# mcu_power.net
KiCad netlist of a schematic drawn in Altium Designer
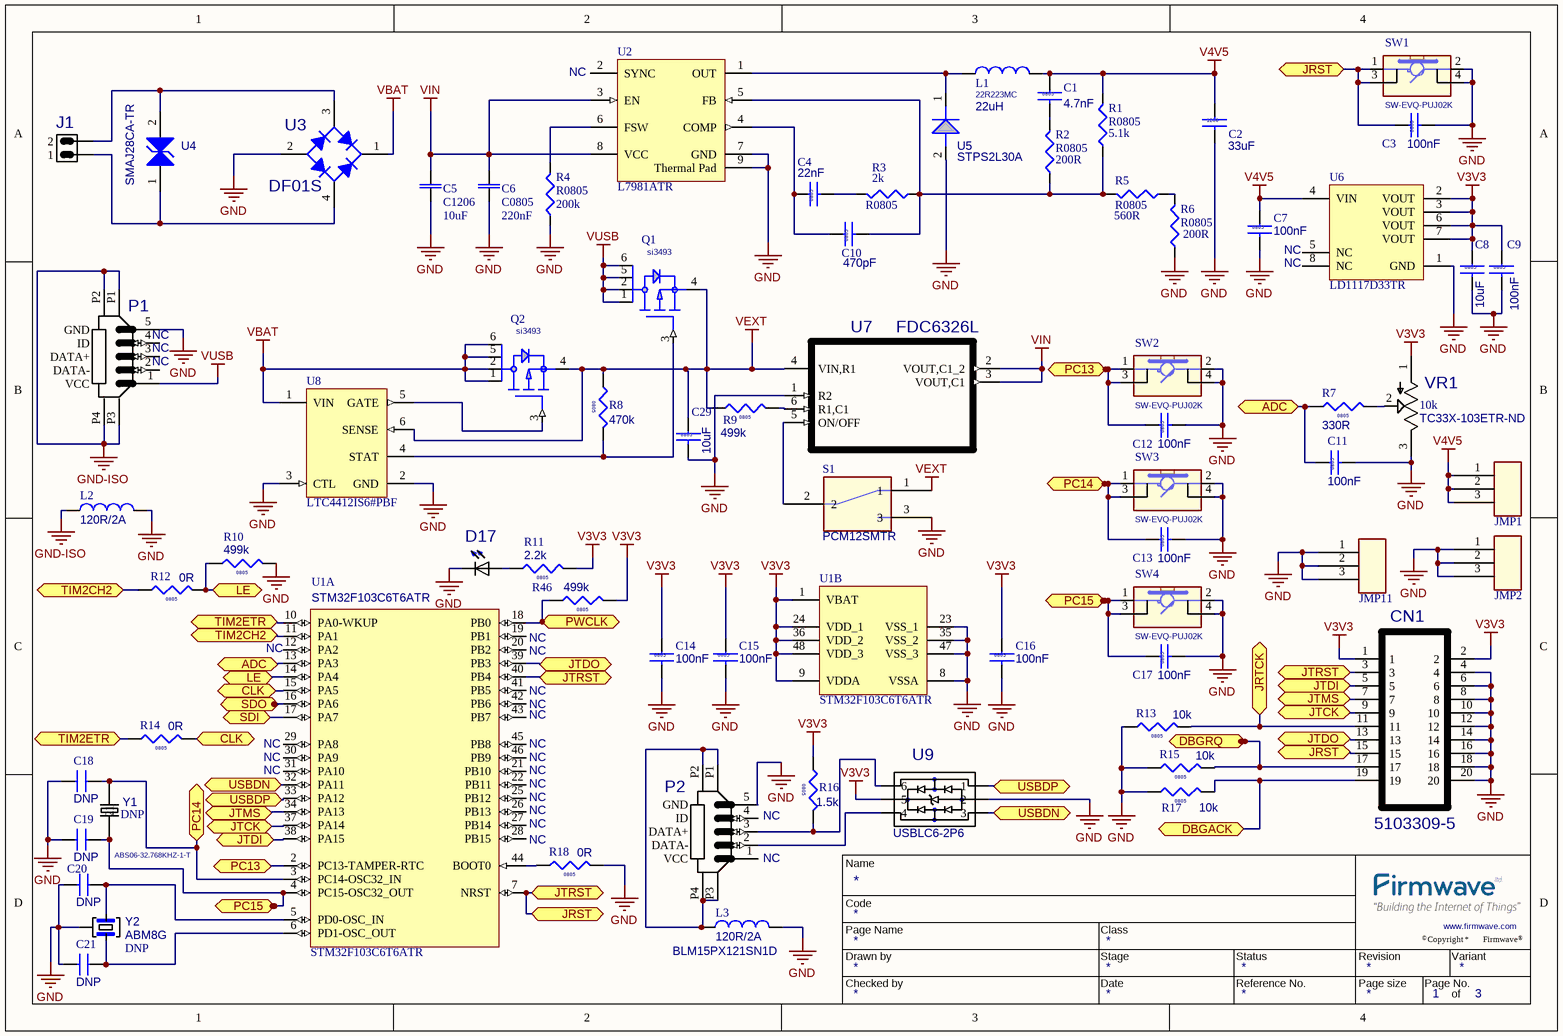
[diagram p0: mcu_power.SchDoc]

(export (version "E")
  (design (tool "Eeschema 10.0.6"))
  (components
    (comp (ref "C1")
      (value "4.7nF")
      (footprint "C0805")
      (fields
        (field (name "TOLERANCE") "±20%")
        (field (name "MANUFACTURER PART NUMBER") "JMK212BJ476MG-T")
        (field (name "MANUFACTURER") "Taiyo Yuden")
      )
      (libsource (lib "Diamond") (part "CAP0805"))
    )
    (comp (ref "C2")
      (value "33uF")
      (footprint "C1206")
      (fields
        (field (name "SELC PARTNUMBER") "SE")
        (field (name "MANUFACTURER") "TDK Corporation")
        (field (name "TOLERANCE") "±20%")
      )
      (libsource (lib "Diamond") (part "CAP1206"))
    )
    (comp (ref "C3")
      (value "100nF")
      (footprint "C0805")
      (fields
        (field (name "TOLERANCE") "±10%")
        (field (name "MANUFACTURER") "Murata Electronics North America")
        (field (name "MANUFACTURER PART NUMBER") "GRM219R71C104KA01D")
      )
      (libsource (lib "Diamond") (part "CAP0805"))
    )
    (comp (ref "C4")
      (value "22nF")
      (footprint "C0805")
      (fields
        (field (name "MANUFACTURER PART NUMBER") "QMK212B7223KG-T")
        (field (name "MANUFACTURER") "Taiyo Yuden")
        (field (name "Comment") "?")
      )
      (libsource (lib "Diamond") (part "CAP0805"))
    )
    (comp (ref "C5")
      (value "C1206")
      (footprint "C1206")
      (description "Capacitor 1206")
      (fields
        (field (name "ALTIUM_VALUE") "10uF")
        (field (name "MANUFACTURER") "TDK Corporation")
        (field (name "TOLERANCE") "±10%")
        (field (name "PUBLISHER") "Firmwave Ltd.")
      )
      (libsource (lib "Diamond") (part "C1206"))
    )
    (comp (ref "C6")
      (value "C0805")
      (footprint "C0805")
      (description "Capacitor 0805")
      (fields
        (field (name "ALTIUM_VALUE") "220nF")
        (field (name "MANUFACTURER") "Taiyo Yuden")
        (field (name "MANUFACTURER PART NUMBER") "UMK212B7224KG-T")
        (field (name "PUBLISHER") "Firmwave Ltd.")
      )
      (libsource (lib "Diamond") (part "C0805"))
    )
    (comp (ref "C7")
      (value "100nF")
      (footprint "C0805")
      (fields
        (field (name "TOLERANCE") "±10%")
        (field (name "MANUFACTURER") "Murata Electronics North America")
        (field (name "MANUFACTURER PART NUMBER") "GRM219R71C104KA01D")
      )
      (libsource (lib "Diamond") (part "CAP0805"))
    )
    (comp (ref "C8")
      (value "10uF")
      (footprint "C0805")
      (fields
        (field (name "TOLERANCE") "±10%")
        (field (name "MANUFACTURER PART NUMBER") "GRM21BR61C106KE15L")
        (field (name "MANUFACTURER") "Murata Electronics North America")
      )
      (libsource (lib "Diamond") (part "CAP0805"))
    )
    (comp (ref "C9")
      (value "100nF")
      (footprint "C0805")
      (fields
        (field (name "TOLERANCE") "±10%")
        (field (name "MANUFACTURER") "Murata Electronics North America")
        (field (name "MANUFACTURER PART NUMBER") "GRM219R71C104KA01D")
      )
      (libsource (lib "Diamond") (part "CAP0805"))
    )
    (comp (ref "C10")
      (value "470pF")
      (footprint "C0805")
      (fields
        (field (name "MANUFACTURER PART NUMBER") "MM051A471JCT2A")
        (field (name "MANUFACTURER") "AVX")
        (field (name "Comment") "?")
      )
      (libsource (lib "Diamond") (part "CAP0805"))
    )
    (comp (ref "C11")
      (value "100nF")
      (footprint "C0805")
      (fields
        (field (name "TOLERANCE") "±10%")
        (field (name "MANUFACTURER") "Murata Electronics North America")
        (field (name "MANUFACTURER PART NUMBER") "GRM219R71C104KA01D")
      )
      (libsource (lib "Diamond") (part "CAP0805"))
    )
    (comp (ref "C12")
      (value "100nF")
      (footprint "C0805")
      (fields
        (field (name "TOLERANCE") "±10%")
        (field (name "MANUFACTURER") "Murata Electronics North America")
        (field (name "MANUFACTURER PART NUMBER") "GRM219R71C104KA01D")
      )
      (libsource (lib "Diamond") (part "CAP0805"))
    )
    (comp (ref "C13")
      (value "100nF")
      (footprint "C0805")
      (fields
        (field (name "TOLERANCE") "±10%")
        (field (name "MANUFACTURER") "Murata Electronics North America")
        (field (name "MANUFACTURER PART NUMBER") "GRM219R71C104KA01D")
      )
      (libsource (lib "Diamond") (part "CAP0805"))
    )
    (comp (ref "C14")
      (value "100nF")
      (footprint "C0805")
      (fields
        (field (name "TOLERANCE") "±10%")
        (field (name "MANUFACTURER") "Murata Electronics North America")
        (field (name "MANUFACTURER PART NUMBER") "GRM219R71C104KA01D")
      )
      (libsource (lib "Diamond") (part "CAP0805"))
    )
    (comp (ref "C15")
      (value "100nF")
      (footprint "C0805")
      (fields
        (field (name "TOLERANCE") "±10%")
        (field (name "MANUFACTURER") "Murata Electronics North America")
        (field (name "MANUFACTURER PART NUMBER") "GRM219R71C104KA01D")
      )
      (libsource (lib "Diamond") (part "CAP0805"))
    )
    (comp (ref "C16")
      (value "100nF")
      (footprint "C0805")
      (fields
        (field (name "TOLERANCE") "±10%")
        (field (name "MANUFACTURER") "Murata Electronics North America")
        (field (name "MANUFACTURER PART NUMBER") "GRM219R71C104KA01D")
      )
      (libsource (lib "Diamond") (part "CAP0805"))
    )
    (comp (ref "C17")
      (value "100nF")
      (footprint "C0805")
      (fields
        (field (name "TOLERANCE") "±10%")
        (field (name "MANUFACTURER") "Murata Electronics North America")
        (field (name "MANUFACTURER PART NUMBER") "GRM219R71C104KA01D")
      )
      (libsource (lib "Diamond") (part "CAP0805"))
    )
    (comp (ref "C18")
      (value "DNP")
      (footprint "0402")
      (description "Ceramic capacitor/SMT0603/16V/20%")
      (fields (field (name "PART") "200xxx") (field (name "Comment") "0402"))
      (libsource (lib "Diamond") (part "C0402_0"))
    )
    (comp (ref "C19")
      (value "DNP")
      (footprint "0402")
      (description "Ceramic capacitor/SMT0603/16V/20%")
      (fields (field (name "PART") "200xxx") (field (name "Comment") "0402"))
      (libsource (lib "Diamond") (part "C0402_0"))
    )
    (comp (ref "C20")
      (value "DNP")
      (footprint "0402")
      (description "Ceramic capacitor/SMT0603/16V/20%")
      (fields (field (name "PART") "200xxx") (field (name "Comment") "0402"))
      (libsource (lib "Diamond") (part "C0402_0"))
    )
    (comp (ref "C21")
      (value "DNP")
      (footprint "0402")
      (description "Ceramic capacitor/SMT0603/16V/20%")
      (fields (field (name "PART") "200xxx") (field (name "Comment") "0402"))
      (libsource (lib "Diamond") (part "C0402_0"))
    )
    (comp (ref "C29")
      (value "10uF")
      (footprint "C0805")
      (fields
        (field (name "TOLERANCE") "±10%")
        (field (name "MANUFACTURER PART NUMBER") "GRM21BR61C106KE15L")
        (field (name "MANUFACTURER") "Murata Electronics North America")
      )
      (libsource (lib "Diamond") (part "CAP0805"))
    )
    (comp (ref "CN1")
      (value "5103309-5")
      (footprint "TYCO_5103309-5")
      (description "Header; Pin; Vertical; Copper Alloy; Thermoplastic; 20; 0.100 x 0.100 in.; 1 A")
      (fields (field (name "MP") "5103309-5") (field (name "MF") "TE Connectivity / AMP"))
      (libsource (lib "Diamond_electromechanical") (part "5103309-5"))
    )
    (comp (ref "D17")
      (value "LTST-C170KGKT")
      (footprint "DIOC200X125X110_LTST-C170KGKT(Primary)")
      (description "Green 2 x 1.25 x 1.1 mm 130Â° Water Clear 35 mcd 2 V Surface Mount LED")
      (fields (field (name "MF") "Lite-On") (field (name "MANUFACTURER PART NUMBER") "LTST-C170KRKT"))
      (libsource (lib "Diamond") (part "LTST-C170KGKT"))
    )
    (comp (ref "J1")
      (value "640455-2")
      (footprint "2-PIN_CONNECTOR")
      (description "MTA-100 2 Position 2.54 mm Single Row Right Angle Wire to Board Header")
      (fields (field (name "MF") "TE Connectivity / AMP"))
      (libsource (lib "Diamond_electromechanical") (part "640455-2"))
    )
    (comp (ref "JMP1")
      (value "JUMPER")
      (footprint "CON-HDR_3X1X254")
      (libsource (lib "Diamond") (part "CON-HDR_3X1X254"))
    )
    (comp (ref "JMP2")
      (value "JUMPER")
      (footprint "CON-HDR_3X1X254")
      (libsource (lib "Diamond") (part "CON-HDR_3X1X254"))
    )
    (comp (ref "JMP11")
      (value "JUMPER")
      (footprint "CON-HDR_3X1X254")
      (libsource (lib "Diamond") (part "CON-HDR_3X1X254"))
    )
    (comp (ref "L1")
      (value "22R223MC")
      (footprint "22R223MC")
      (fields (field (name "MANUFACTURER") "Murata Power Solutions") (field (name "ALTIUM_VALUE") "22uH"))
      (libsource (lib "Diamond") (part "22R223MC"))
    )
    (comp (ref "L2")
      (value "120R/2A")
      (footprint "0402")
      (description "BLM15PX121SN1D")
      (fields
        (field (name "SELC PARTNUMBER") "SE?")
        (field (name "MANUFACTURER") "Murata Electronics North America")
      )
      (libsource (lib "Diamond") (part "IND0402"))
    )
    (comp (ref "L3")
      (value "120R/2A")
      (footprint "0402")
      (description "BLM15PX121SN1D")
      (fields
        (field (name "SELC PARTNUMBER") "SE?")
        (field (name "MANUFACTURER") "Murata Electronics North America")
        (field (name "MANUFACTURER PART NUMBER") "BLM15PX121SN1D")
      )
      (libsource (lib "Diamond") (part "IND0402"))
    )
    (comp (ref "P1")
      (value "440247-2")
      (footprint "TE_440247-2")
      (fields (field (name "MF") "Micross") (field (name "MANUFACTURER") "TE Connectivity AMP Connectors"))
      (libsource (lib "Diamond_electromechanical") (part "440247-2"))
    )
    (comp (ref "P2")
      (value "440247-2")
      (footprint "TE_440247-2")
      (fields (field (name "MF") "Micross") (field (name "MANUFACTURER") "TE Connectivity AMP Connectors"))
      (libsource (lib "Diamond_electromechanical") (part "440247-2"))
    )
    (comp (ref "Q1")
      (value "si3493")
      (footprint "TSOP-6")
      (fields
        (field (name "MANUFACTURER PART NUMBER") "SI3493BDV-T1-E3")
        (field (name "MANUFACTURER") "Vishay Siliconix")
      )
      (libsource (lib "Diamond") (part "SI3493DBV"))
    )
    (comp (ref "Q2")
      (value "si3493")
      (footprint "TSOP-6")
      (fields
        (field (name "MANUFACTURER PART NUMBER") "SI3493BDV-T1-E3")
        (field (name "MANUFACTURER") "Vishay Siliconix")
      )
      (libsource (lib "Diamond") (part "SI3493DBV"))
    )
    (comp (ref "R1")
      (value "R0805")
      (footprint "R0805")
      (fields
        (field (name "ALTIUM_VALUE") "5.1k")
        (field (name "MANUFACTURER") "Panasonic Electronic Components")
        (field (name "MANUFACTURER PART NUMBER") "ERJ-6GEYJ512V")
        (field (name "TOLERANCE") "±5%")
        (field (name "PUBLISHER") "Firmwave Limited")
      )
      (libsource (lib "Diamond") (part "R0805"))
    )
    (comp (ref "R2")
      (value "R0805")
      (footprint "R0805")
      (fields
        (field (name "ALTIUM_VALUE") "200R")
        (field (name "MANUFACTURER") "Panasonic Electronic Components")
        (field (name "TOLERANCE") "±5%")
        (field (name "MANUFACTURER PART NUMBER") "ERJ-6GEYJ201V")
        (field (name "PUBLISHER") "Firmwave Limited")
      )
      (libsource (lib "Diamond") (part "R0805"))
    )
    (comp (ref "R3")
      (value "R0805")
      (footprint "R0805")
      (fields
        (field (name "ALTIUM_VALUE") "2k")
        (field (name "TOLERANCE") "±5%")
        (field (name "MANUFACTURER PART NUMBER") "ERJ-6GEYJ202V")
        (field (name "MANUFACTURER") "Panasonic Electronic Components")
        (field (name "PUBLISHER") "Firmwave Limited")
      )
      (libsource (lib "Diamond") (part "R0805"))
    )
    (comp (ref "R4")
      (value "R0805")
      (footprint "R0805")
      (fields
        (field (name "ALTIUM_VALUE") "200k")
        (field (name "MANUFACTURER") "Panasonic Electronic Components")
        (field (name "MANUFACTURER PART NUMBER") "ERJ-6GEYJ204V")
        (field (name "TOLERANCE") "±5%")
        (field (name "PUBLISHER") "Firmwave Limited")
      )
      (libsource (lib "Diamond") (part "R0805"))
    )
    (comp (ref "R5")
      (value "R0805")
      (footprint "R0805")
      (fields
        (field (name "ALTIUM_VALUE") "560R")
        (field (name "MANUFACTURER") "Panasonic Electronic Components")
        (field (name "TOLERANCE") "±5%")
        (field (name "MANUFACTURER PART NUMBER") "ERJ-6GEYJ561V")
        (field (name "PUBLISHER") "Firmwave Limited")
      )
      (libsource (lib "Diamond") (part "R0805"))
    )
    (comp (ref "R6")
      (value "R0805")
      (footprint "R0805")
      (fields
        (field (name "ALTIUM_VALUE") "200R")
        (field (name "MANUFACTURER") "Panasonic")
        (field (name "MANUFACTURER PART NUMBER") "ERJ-6ENF2200V")
        (field (name "PUBLISHER") "Firmwave Limited")
      )
      (libsource (lib "Diamond") (part "R0805"))
    )
    (comp (ref "R7")
      (value "330R")
      (footprint "R0805")
      (fields
        (field (name "TOLERANCE") "±5%")
        (field (name "MANUFACTURER PART NUMBER") "ERJ-6GEYJ331V")
        (field (name "MANUFACTURER") "Panasonic Electronic Components")
      )
      (libsource (lib "Diamond") (part "RES0805"))
    )
    (comp (ref "R8")
      (value "470k")
      (footprint "R0805")
      (fields
        (field (name "TOLERANCE") "±5%")
        (field (name "MANUFACTURER PART NUMBER") "RCV0805470KJNEA")
        (field (name "MANUFACTURER") "Vishay BC Components")
      )
      (libsource (lib "Diamond") (part "RES0805"))
    )
    (comp (ref "R9")
      (value "499k")
      (footprint "R0805")
      (fields
        (field (name "MANUFACTURER") "Rohm Semiconductor")
        (field (name "TOLERANCE") "±1%")
        (field (name "MANUFACTURER PART NUMBER") "KTR10EZPF4993")
      )
      (libsource (lib "Diamond") (part "RES0805"))
    )
    (comp (ref "R10")
      (value "499k")
      (footprint "R0805")
      (fields
        (field (name "MANUFACTURER") "Rohm Semiconductor")
        (field (name "TOLERANCE") "±1%")
        (field (name "MANUFACTURER PART NUMBER") "KTR10EZPF4993")
      )
      (libsource (lib "Diamond") (part "RES0805"))
    )
    (comp (ref "R11")
      (value "2.2k")
      (footprint "R0805")
      (fields
        (field (name "MANUFACTURER") "Vishay")
        (field (name "TOLERANCE") "±1%")
        (field (name "MANUFACTURER PART NUMBER") "CRCW08052K20FKEA")
      )
      (libsource (lib "Diamond") (part "RES0805"))
    )
    (comp (ref "R12")
      (value "0R")
      (footprint "R0805")
      (fields
        (field (name "MANUFACTURER PART NUMBER") "CRCW08050000Z0EA")
        (field (name "MANUFACTURER") "Vishay Dale")
        (field (name "TOLERANCE") "Jumper")
      )
      (libsource (lib "Diamond") (part "RES0805"))
    )
    (comp (ref "R13")
      (value "10k")
      (footprint "R0805")
      (fields
        (field (name "MANUFACTURER PART NUMBER") "CRCW080510K0FKEA")
        (field (name "TOLERANCE") "±1%")
        (field (name "MANUFACTURER") "Vishay Dale")
      )
      (libsource (lib "Diamond") (part "RES0805"))
    )
    (comp (ref "R14")
      (value "0R")
      (footprint "R0805")
      (fields
        (field (name "MANUFACTURER PART NUMBER") "CRCW08050000Z0EA")
        (field (name "MANUFACTURER") "Vishay Dale")
        (field (name "TOLERANCE") "Jumper")
      )
      (libsource (lib "Diamond") (part "RES0805"))
    )
    (comp (ref "R15")
      (value "10k")
      (footprint "R0805")
      (fields
        (field (name "MANUFACTURER PART NUMBER") "CRCW080510K0FKEA")
        (field (name "TOLERANCE") "±1%")
        (field (name "MANUFACTURER") "Vishay Dale")
      )
      (libsource (lib "Diamond") (part "RES0805"))
    )
    (comp (ref "R16")
      (value "1.5k")
      (footprint "R0805")
      (fields
        (field (name "MANUFACTURER") "Vishay Dale")
        (field (name "TOLERANCE") "±1%")
        (field (name "MANUFACTURER PART NUMBER") "CRCW08051K50FKEA")
      )
      (libsource (lib "Diamond") (part "RES0805"))
    )
    (comp (ref "R17")
      (value "10k")
      (footprint "R0805")
      (fields
        (field (name "MANUFACTURER PART NUMBER") "CRCW080510K0FKEA")
        (field (name "TOLERANCE") "±1%")
        (field (name "MANUFACTURER") "Vishay Dale")
      )
      (libsource (lib "Diamond") (part "RES0805"))
    )
    (comp (ref "R18")
      (value "0R")
      (footprint "R0805")
      (fields
        (field (name "MANUFACTURER PART NUMBER") "CRCW08050000Z0EA")
        (field (name "MANUFACTURER") "Vishay Dale")
        (field (name "TOLERANCE") "Jumper")
      )
      (libsource (lib "Diamond") (part "RES0805"))
    )
    (comp (ref "R46")
      (value "499k")
      (footprint "R0805")
      (fields
        (field (name "MANUFACTURER") "Rohm Semiconductor")
        (field (name "TOLERANCE") "±1%")
        (field (name "MANUFACTURER PART NUMBER") "KTR10EZPF4993")
      )
      (libsource (lib "Diamond") (part "RES0805"))
    )
    (comp (ref "S1")
      (value "SW_ON_OFF_Mini")
      (footprint "PCM12SMTR")
      (fields (field (name "MANUFACTURER PART NUMBER") "PCM12SMTR") (field (name "MANUFACTURER") "C&K"))
      (libsource (lib "Diamond") (part "SW_ON_OFF_Mini"))
    )
    (comp (ref "SW1")
      (value "SW-EVQ-PUJ02K")
      (footprint "EVQPUJ02K")
      (description "EVQ-PUJ02K")
      (fields (field (name "MANUFACTURER") "Panasonic Electronic Components"))
      (libsource (lib "Diamond") (part "SW-EVQ-PUJ02K"))
    )
    (comp (ref "SW2")
      (value "SW-EVQ-PUJ02K")
      (footprint "EVQPUJ02K")
      (description "EVQ-PUJ02K")
      (fields (field (name "MANUFACTURER") "Panasonic Electronic Components"))
      (libsource (lib "Diamond") (part "SW-EVQ-PUJ02K"))
    )
    (comp (ref "SW3")
      (value "SW-EVQ-PUJ02K")
      (footprint "EVQPUJ02K")
      (description "EVQ-PUJ02K")
      (fields (field (name "MANUFACTURER") "Panasonic Electronic Components"))
      (libsource (lib "Diamond") (part "SW-EVQ-PUJ02K"))
    )
    (comp (ref "SW4")
      (value "SW-EVQ-PUJ02K")
      (footprint "EVQPUJ02K")
      (description "EVQ-PUJ02K")
      (fields (field (name "MANUFACTURER") "Panasonic Electronic Components"))
      (libsource (lib "Diamond") (part "SW-EVQ-PUJ02K"))
    )
    (comp (ref "U1")
      (value "STM32F103C6T6ATR")
      (footprint "STM-LQFP48_N")
      (fields
        (field (name "MANUFACTURER PART NUMBER") "STM32F103C6T6ATR")
        (field (name "MANUFACTURER") "STMicroelectronics")
      )
      (libsource (lib "STMicroelectronics STM32 F1") (part "STM32F103C6T6ATR"))
    )
    (comp (ref "U2")
      (value "L7981ATR")
      (footprint "HSOP8-D1_N")
      (description "3 A step-down switching regulator, 8-Pin HSOP, Tape and Reel")
      (fields (field (name "MANUFACTURER") "STMicroelectronics"))
      (libsource (lib "STMicroelectronics Power Management DC-DC Conversion") (part "L7981ATR"))
    )
    (comp (ref "U3")
      (value "DF01S")
      (footprint "SOT508P985X260-4N")
      (description "Power Management, Bridge Rectifiers, Semiconductors and Actives")
      (fields
        (field (name "MF") "International Rectifier")
        (field (name "MANUFACTURER") "Vishay Semiconductor")
      )
      (libsource (lib "Diamond") (part "DF01S"))
    )
    (comp (ref "U4")
      (value "SMAJ28CA-TR")
      (footprint "DO-214AA")
      (fields (field (name "MANUFACTURER") "STMICROELECTRONICS"))
      (libsource (lib "Diamond") (part "SMAJ28CA-TR"))
    )
    (comp (ref "U5")
      (value "STPS2L30A")
      (footprint "DO-214AA")
      (fields (field (name "MANUFACTURER") "NXP Semiconductors") (field (name "MPN") "BGU7005"))
      (libsource (lib "Diamond") (part "STPS2L30A"))
    )
    (comp (ref "U6")
      (value "LD1117D33TR")
      (footprint "SO8_N")
      (description "Fixed Low Drop Positive Voltage Regulator, 3.3V, 8-Pin SO, Tape and Reel")
      (fields
        (field (name "MANUFACTURER PART NUMBER") "STPS2L30A")
        (field (name "MANUFACTURER") "STMicroelectronics")
      )
      (libsource (lib "STMicroelectronics Power Management Linear Regulator") (part "LD1117D33TR"))
    )
    (comp (ref "U7")
      (value "FDC6326L")
      (footprint "SOT95P280X110-6N")
      (description "FDC6326L Series 20 V 0.125 Ohm Surface Mount Integrated Load Switch -SuperSOT-6")
      (fields
        (field (name "MF") "Fairchild Semiconductor")
        (field (name "MANUFACTURER PART NUMBER") "FDC6331L")
      )
      (libsource (lib "Diamond_semiconductors") (part "FDC6326L"))
    )
    (comp (ref "U8")
      (value "LTC4412IS6#PBF")
      (footprint "LT-S6-6-TSOT-23_N")
      (description "Low Loss PowerPath(TM) Controller, 2.5 to 28 V Vin, 6-pin SOT23 (S6-6), -40 to 85 degC, Pb-Free")
      (fields (field (name "MANUFACTURER") "Linear Technology"))
      (libsource (lib "Linear Technology Power Management Power Control") (part "LTC4412IS6#PBF"))
    )
    (comp (ref "U9")
      (value "USBLC6-2")
      (footprint "USBLC6-2P6")
      (description "Very Low Capacitance Esd Protection")
      (fields (field (name "MF") "STMicroelectronics") (field (name "MANUFACTURER PART NUMBER") "USBLC6-2P6"))
      (libsource (lib "Diamond") (part "USBLC6-2"))
    )
    (comp (ref "VR1")
      (value "10k")
      (footprint "TRIM_TC33X-2-103E")
      (description "Res Trimmer 10K Ohm 25% 0.1W(1/10W) 1(Elec)/1(Mech)Turn (3 X 3.8mm) Foot Print SMD Embossed T/R")
      (fields
        (field (name "MP") "TC33X-2-103E")
        (field (name "MF") "Bourns")
        (field (name "SUPPLIER PART NUMBER") "TC33X-103ETR-ND")
      )
      (libsource (lib "Diamond_passive") (part "TC33X-2-103E"))
    )
    (comp (ref "Y1")
      (value "ABS06-32.768KHZ-1-T")
      (footprint "XTAL_ABS06-32.768KHZ-1-T")
      (fields (field (name "ALTIUM_VALUE") "DNP"))
      (libsource (lib "Diamond") (part "ABS06-32.768KHZ-1-T"))
    )
    (comp (ref "Y2")
      (value "ABM8G")
      (footprint "ABM8G_ABM8G(Primary)")
      (fields (field (name "ALTIUM_VALUE") "DNP"))
      (libsource (lib "Diamond") (part "ABM8G"))
    )
  )
  (nets
    (net (code "1") (name "/ADC") (class "Default")
      (node (ref "C11") (pin "1") (pinfunction "1_1") (pintype "passive"))
      (node (ref "R7") (pin "1") (pinfunction "1_1") (pintype "passive"))
      (node (ref "U1") (pin "13") (pinfunction "PA3_13") (pintype "bidirectional"))
    )
    (net (code "2") (name "/CLK") (class "Default")
      (node (ref "R14") (pin "2") (pinfunction "2_2") (pintype "passive"))
      (node (ref "U1") (pin "15") (pinfunction "PA5_15") (pintype "bidirectional"))
    )
    (net (code "3") (name "/DBGACK") (class "Default")
      (node (ref "CN1") (pin "19") (pinfunction "19_19") (pintype "passive"))
      (node (ref "R17") (pin "2") (pinfunction "2_2") (pintype "passive"))
    )
    (net (code "4") (name "/DBGRQ") (class "Default")
      (node (ref "CN1") (pin "17") (pinfunction "17_17") (pintype "passive"))
      (node (ref "R15") (pin "2") (pinfunction "2_2") (pintype "passive"))
    )
    (net (code "5") (name "/JRST") (class "Default")
      (node (ref "C3") (pin "1") (pinfunction "1_1") (pintype "passive"))
      (node (ref "CN1") (pin "15") (pinfunction "15_15") (pintype "passive"))
      (node (ref "CN1") (pin "3") (pinfunction "3_3") (pintype "passive"))
      (node (ref "SW1") (pin "1") (pinfunction "1_1") (pintype "passive"))
      (node (ref "SW1") (pin "3") (pinfunction "3_3") (pintype "passive"))
      (node (ref "U1") (pin "40") (pinfunction "PB4_40") (pintype "bidirectional"))
      (node (ref "U1") (pin "7") (pinfunction "NRST_7") (pintype "bidirectional"))
    )
    (net (code "6") (name "/JRTCK") (class "Default")
      (node (ref "CN1") (pin "11") (pinfunction "11_11") (pintype "passive"))
      (node (ref "R13") (pin "2") (pinfunction "2_2") (pintype "passive"))
    )
    (net (code "7") (name "/JTCK") (class "Default")
      (node (ref "CN1") (pin "9") (pinfunction "9_9") (pintype "passive"))
      (node (ref "U1") (pin "37") (pinfunction "PA14_37") (pintype "bidirectional"))
    )
    (net (code "8") (name "/JTDI") (class "Default")
      (node (ref "CN1") (pin "5") (pinfunction "5_5") (pintype "passive"))
      (node (ref "U1") (pin "38") (pinfunction "PA15_38") (pintype "bidirectional"))
    )
    (net (code "9") (name "/JTDO") (class "Default")
      (node (ref "CN1") (pin "13") (pinfunction "13_13") (pintype "passive"))
      (node (ref "U1") (pin "39") (pinfunction "PB3_39") (pintype "bidirectional"))
    )
    (net (code "10") (name "/JTMS") (class "Default")
      (node (ref "CN1") (pin "7") (pinfunction "7_7") (pintype "passive"))
      (node (ref "U1") (pin "34") (pinfunction "PA13_34") (pintype "bidirectional"))
    )
    (net (code "11") (name "/LE") (class "Default")
      (node (ref "R10") (pin "1") (pinfunction "1_1") (pintype "passive"))
      (node (ref "R12") (pin "2") (pinfunction "2_2") (pintype "passive"))
      (node (ref "U1") (pin "14") (pinfunction "PA4_14") (pintype "bidirectional"))
    )
    (net (code "12") (name "/PC13") (class "Default")
      (node (ref "C12") (pin "1") (pinfunction "1_1") (pintype "passive"))
      (node (ref "SW2") (pin "1") (pinfunction "1_1") (pintype "passive"))
      (node (ref "SW2") (pin "3") (pinfunction "3_3") (pintype "passive"))
      (node (ref "U1") (pin "2") (pinfunction "PC13-TAMPER-RTC_2") (pintype "bidirectional"))
    )
    (net (code "13") (name "/PC14") (class "Default")
      (node (ref "C13") (pin "1") (pinfunction "1_1") (pintype "passive"))
      (node (ref "C18") (pin "2") (pinfunction "2_2") (pintype "passive"))
      (node (ref "SW3") (pin "1") (pinfunction "1_1") (pintype "passive"))
      (node (ref "SW3") (pin "3") (pinfunction "3_3") (pintype "passive"))
      (node (ref "U1") (pin "3") (pinfunction "PC14-OSC32_IN_3") (pintype "bidirectional"))
      (node (ref "Y1") (pin "1") (pinfunction "1_1") (pintype "passive"))
    )
    (net (code "14") (name "/PC15") (class "Default")
      (node (ref "C17") (pin "1") (pinfunction "1_1") (pintype "passive"))
      (node (ref "C19") (pin "2") (pinfunction "2_2") (pintype "passive"))
      (node (ref "SW4") (pin "1") (pinfunction "1_1") (pintype "passive"))
      (node (ref "SW4") (pin "3") (pinfunction "3_3") (pintype "passive"))
      (node (ref "U1") (pin "4") (pinfunction "PC15-OSC32_OUT_4") (pintype "bidirectional"))
      (node (ref "Y1") (pin "2") (pinfunction "2_2") (pintype "passive"))
    )
    (net (code "15") (name "/PWCLK") (class "Default")
      (node (ref "R46") (pin "1") (pinfunction "1_1") (pintype "passive"))
      (node (ref "U1") (pin "18") (pinfunction "PB0_18") (pintype "bidirectional"))
    )
    (net (code "16") (name "/SDI") (class "Default")
      (node (ref "U1") (pin "17") (pinfunction "PA7_17") (pintype "bidirectional"))
    )
    (net (code "17") (name "/SDO") (class "Default")
      (node (ref "U1") (pin "16") (pinfunction "PA6_16") (pintype "bidirectional"))
    )
    (net (code "18") (name "/TIM2CH2") (class "Default")
      (node (ref "R12") (pin "1") (pinfunction "1_1") (pintype "passive"))
      (node (ref "U1") (pin "11") (pinfunction "PA1_11") (pintype "bidirectional"))
    )
    (net (code "19") (name "/TIM2ETR") (class "Default")
      (node (ref "R14") (pin "1") (pinfunction "1_1") (pintype "passive"))
      (node (ref "U1") (pin "10") (pinfunction "PA0-WKUP_10") (pintype "bidirectional"))
    )
    (net (code "20") (name "/USBDN") (class "Default")
      (node (ref "U1") (pin "32") (pinfunction "PA11_32") (pintype "bidirectional"))
      (node (ref "U9") (pin "3") (pinfunction "3_3") (pintype "bidirectional"))
    )
    (net (code "21") (name "/USBDP") (class "Default")
      (node (ref "U1") (pin "33") (pinfunction "PA12_33") (pintype "bidirectional"))
      (node (ref "U9") (pin "1") (pinfunction "1_1") (pintype "bidirectional"))
    )
    (net (code "22") (name "GND") (class "Default")
      (node (ref "C11") (pin "2") (pinfunction "2_2") (pintype "passive"))
      (node (ref "C12") (pin "2") (pinfunction "2_2") (pintype "passive"))
      (node (ref "C13") (pin "2") (pinfunction "2_2") (pintype "passive"))
      (node (ref "C14") (pin "2") (pinfunction "2_2") (pintype "passive"))
      (node (ref "C15") (pin "2") (pinfunction "2_2") (pintype "passive"))
      (node (ref "C16") (pin "2") (pinfunction "2_2") (pintype "passive"))
      (node (ref "C17") (pin "2") (pinfunction "2_2") (pintype "passive"))
      (node (ref "C18") (pin "1") (pinfunction "1_1") (pintype "passive"))
      (node (ref "C19") (pin "1") (pinfunction "1_1") (pintype "passive"))
      (node (ref "C2") (pin "2") (pinfunction "2_2") (pintype "passive"))
      (node (ref "C20") (pin "1") (pinfunction "1_1") (pintype "passive"))
      (node (ref "C21") (pin "1") (pinfunction "1_1") (pintype "passive"))
      (node (ref "C29") (pin "2") (pinfunction "2_2") (pintype "passive"))
      (node (ref "C3") (pin "2") (pinfunction "2_2") (pintype "passive"))
      (node (ref "C5") (pin "1") (pinfunction "1_1") (pintype "passive"))
      (node (ref "C6") (pin "1") (pinfunction "1_1") (pintype "passive"))
      (node (ref "C7") (pin "2") (pinfunction "2_2") (pintype "passive"))
      (node (ref "C8") (pin "2") (pinfunction "2_2") (pintype "passive"))
      (node (ref "C9") (pin "2") (pinfunction "2_2") (pintype "passive"))
      (node (ref "CN1") (pin "10") (pinfunction "10_10") (pintype "passive"))
      (node (ref "CN1") (pin "12") (pinfunction "12_12") (pintype "passive"))
      (node (ref "CN1") (pin "14") (pinfunction "14_14") (pintype "passive"))
      (node (ref "CN1") (pin "16") (pinfunction "16_16") (pintype "passive"))
      (node (ref "CN1") (pin "18") (pinfunction "18_18") (pintype "passive"))
      (node (ref "CN1") (pin "20") (pinfunction "20_20") (pintype "passive"))
      (node (ref "CN1") (pin "4") (pinfunction "4_4") (pintype "passive"))
      (node (ref "CN1") (pin "6") (pinfunction "6_6") (pintype "passive"))
      (node (ref "CN1") (pin "8") (pinfunction "8_8") (pintype "passive"))
      (node (ref "D17") (pin "1") (pinfunction "1_1") (pintype "passive"))
      (node (ref "JMP11") (pin "1") (pinfunction "1_1") (pintype "passive"))
      (node (ref "JMP11") (pin "2") (pinfunction "2_2") (pintype "passive"))
      (node (ref "JMP11") (pin "3") (pinfunction "3_3") (pintype "passive"))
      (node (ref "JMP2") (pin "1") (pinfunction "1_1") (pintype "passive"))
      (node (ref "JMP2") (pin "2") (pinfunction "2_2") (pintype "passive"))
      (node (ref "JMP2") (pin "3") (pinfunction "3_3") (pintype "passive"))
      (node (ref "L2") (pin "2") (pinfunction "2_2") (pintype "passive"))
      (node (ref "L3") (pin "2") (pinfunction "2_2") (pintype "passive"))
      (node (ref "P1") (pin "5") (pinfunction "GND_5") (pintype "passive"))
      (node (ref "P2") (pin "5") (pinfunction "GND_5") (pintype "passive"))
      (node (ref "R10") (pin "2") (pinfunction "2_2") (pintype "passive"))
      (node (ref "R13") (pin "1") (pinfunction "1_1") (pintype "passive"))
      (node (ref "R15") (pin "1") (pinfunction "1_1") (pintype "passive"))
      (node (ref "R17") (pin "1") (pinfunction "1_1") (pintype "passive"))
      (node (ref "R18") (pin "2") (pinfunction "2_2") (pintype "passive"))
      (node (ref "R4") (pin "1") (pinfunction "1_1") (pintype "passive"))
      (node (ref "R6") (pin "1") (pinfunction "1_1") (pintype "passive"))
      (node (ref "S1") (pin "3") (pinfunction "3_3") (pintype "passive"))
      (node (ref "SW1") (pin "2") (pinfunction "2_2") (pintype "passive"))
      (node (ref "SW1") (pin "4") (pinfunction "4_4") (pintype "passive"))
      (node (ref "SW2") (pin "2") (pinfunction "2_2") (pintype "passive"))
      (node (ref "SW2") (pin "4") (pinfunction "4_4") (pintype "passive"))
      (node (ref "SW3") (pin "2") (pinfunction "2_2") (pintype "passive"))
      (node (ref "SW3") (pin "4") (pinfunction "4_4") (pintype "passive"))
      (node (ref "SW4") (pin "2") (pinfunction "2_2") (pintype "passive"))
      (node (ref "SW4") (pin "4") (pinfunction "4_4") (pintype "passive"))
      (node (ref "U1") (pin "23") (pinfunction "VSS_1_23") (pintype "power_in"))
      (node (ref "U1") (pin "35") (pinfunction "VSS_2_35") (pintype "power_in"))
      (node (ref "U1") (pin "47") (pinfunction "VSS_3_47") (pintype "power_in"))
      (node (ref "U1") (pin "8") (pinfunction "VSSA_8") (pintype "power_in"))
      (node (ref "U2") (pin "7") (pinfunction "GND_7") (pintype "power_in"))
      (node (ref "U2") (pin "9") (pinfunction "Thermal_Pad_9") (pintype "power_in"))
      (node (ref "U3") (pin "2") (pinfunction "A_2") (pintype "passive"))
      (node (ref "U5") (pin "2") (pinfunction "ANODE_2") (pintype "passive"))
      (node (ref "U6") (pin "1") (pinfunction "GND_1") (pintype "power_in"))
      (node (ref "U7") (pin "1") (pinfunction "R2_1") (pintype "input"))
      (node (ref "U8") (pin "2") (pinfunction "GND_2") (pintype "power_in"))
      (node (ref "U8") (pin "3") (pinfunction "CTL_3") (pintype "input"))
      (node (ref "U9") (pin "2") (pinfunction "2_2") (pintype "power_in"))
      (node (ref "VR1") (pin "3") (pinfunction "3_3") (pintype "passive"))
      (node (ref "Y2") (pin "2_4") (pinfunction "2_2_4") (pintype "passive"))
    )
    (net (code "23") (name "GND-ISO") (class "Default")
      (node (ref "L2") (pin "1") (pinfunction "1_1") (pintype "passive"))
      (node (ref "P1") (pin "P1") (pinfunction "GND_P1") (pintype "passive"))
      (node (ref "P1") (pin "P2") (pinfunction "GND_P2") (pintype "passive"))
      (node (ref "P1") (pin "P3") (pinfunction "GND_P3") (pintype "passive"))
      (node (ref "P1") (pin "P4") (pinfunction "GND_P4") (pintype "passive"))
    )
    (net (code "24") (name "Net-(C1-Pad2)") (class "Default")
      (node (ref "C1") (pin "2") (pinfunction "2_2") (pintype "passive"))
      (node (ref "R2") (pin "2") (pinfunction "2_2") (pintype "passive"))
    )
    (net (code "25") (name "Net-(C4-Pad2)") (class "Default")
      (node (ref "C4") (pin "2") (pinfunction "2_2") (pintype "passive"))
      (node (ref "R3") (pin "2") (pinfunction "2_2") (pintype "passive"))
    )
    (net (code "26") (name "Net-(D17-Pad2)") (class "Default")
      (node (ref "D17") (pin "2") (pinfunction "2_2") (pintype "passive"))
      (node (ref "R11") (pin "1") (pinfunction "1_1") (pintype "passive"))
    )
    (net (code "27") (name "Net-(J1-Pad1)") (class "Default")
      (node (ref "J1") (pin "1") (pinfunction "1_1") (pintype "passive"))
      (node (ref "U3") (pin "4") (pinfunction "C_4") (pintype "passive"))
      (node (ref "U4") (pin "1") (pinfunction "C_1") (pintype "passive"))
    )
    (net (code "28") (name "Net-(J1-Pad2)") (class "Default")
      (node (ref "J1") (pin "2") (pinfunction "2_2") (pintype "passive"))
      (node (ref "U3") (pin "3") (pinfunction "C_3") (pintype "passive"))
      (node (ref "U4") (pin "2") (pinfunction "C_2") (pintype "passive"))
    )
    (net (code "29") (name "Net-(L3-Pad1)") (class "Default")
      (node (ref "L3") (pin "1") (pinfunction "1_1") (pintype "passive"))
      (node (ref "P2") (pin "P1") (pinfunction "GND_P1") (pintype "passive"))
      (node (ref "P2") (pin "P2") (pinfunction "GND_P2") (pintype "passive"))
      (node (ref "P2") (pin "P3") (pinfunction "GND_P3") (pintype "passive"))
      (node (ref "P2") (pin "P4") (pinfunction "GND_P4") (pintype "passive"))
    )
    (net (code "30") (name "Net-(P2-DATA+)") (class "Default")
      (node (ref "P2") (pin "3") (pinfunction "DATA+_3") (pintype "bidirectional"))
      (node (ref "R16") (pin "2") (pinfunction "2_2") (pintype "passive"))
      (node (ref "U9") (pin "6") (pinfunction "6_6") (pintype "bidirectional"))
    )
    (net (code "31") (name "Net-(P2-DATA-)") (class "Default")
      (node (ref "P2") (pin "2") (pinfunction "DATA-_2") (pintype "bidirectional"))
      (node (ref "U9") (pin "4") (pinfunction "4_4") (pintype "bidirectional"))
    )
    (net (code "32") (name "Net-(Q1-G)") (class "Default")
      (node (ref "Q1") (pin "3") (pinfunction "G_3") (pintype "input"))
      (node (ref "R8") (pin "2") (pinfunction "2_2") (pintype "passive"))
      (node (ref "U8") (pin "4") (pinfunction "STAT_4") (pintype "open_collector"))
    )
    (net (code "33") (name "Net-(Q2-G)") (class "Default")
      (node (ref "Q2") (pin "3") (pinfunction "G_3") (pintype "input"))
      (node (ref "U8") (pin "5") (pinfunction "GATE_5") (pintype "output"))
    )
    (net (code "34") (name "Net-(R5-Pad1)") (class "Default")
      (node (ref "R5") (pin "1") (pinfunction "1_1") (pintype "passive"))
      (node (ref "R6") (pin "2") (pinfunction "2_2") (pintype "passive"))
    )
    (net (code "35") (name "Net-(R7-Pad2)") (class "Default")
      (node (ref "R7") (pin "2") (pinfunction "2_2") (pintype "passive"))
      (node (ref "VR1") (pin "2") (pinfunction "2_2") (pintype "passive"))
    )
    (net (code "36") (name "Net-(U1A-BOOT0)") (class "Default")
      (node (ref "R18") (pin "1") (pinfunction "1_1") (pintype "passive"))
      (node (ref "U1") (pin "44") (pinfunction "BOOT0_44") (pintype "input"))
    )
    (net (code "37") (name "Net-(U1A-PD0-OSC_IN)") (class "Default")
      (node (ref "C20") (pin "2") (pinfunction "2_2") (pintype "passive"))
      (node (ref "U1") (pin "5") (pinfunction "PD0-OSC_IN_5") (pintype "bidirectional"))
      (node (ref "Y2") (pin "1") (pinfunction "1_1") (pintype "passive"))
    )
    (net (code "38") (name "Net-(U1A-PD1-OSC_OUT)") (class "Default")
      (node (ref "C21") (pin "2") (pinfunction "2_2") (pintype "passive"))
      (node (ref "U1") (pin "6") (pinfunction "PD1-OSC_OUT_6") (pintype "bidirectional"))
      (node (ref "Y2") (pin "3") (pinfunction "3_3") (pintype "passive"))
    )
    (net (code "39") (name "Net-(U2-COMP)") (class "Default")
      (node (ref "C10") (pin "1") (pinfunction "1_1") (pintype "passive"))
      (node (ref "C4") (pin "1") (pinfunction "1_1") (pintype "passive"))
      (node (ref "U2") (pin "4") (pinfunction "COMP_4") (pintype "output"))
    )
    (net (code "40") (name "Net-(U2-FB)") (class "Default")
      (node (ref "C10") (pin "2") (pinfunction "2_2") (pintype "passive"))
      (node (ref "R1") (pin "1") (pinfunction "1_1") (pintype "passive"))
      (node (ref "R2") (pin "1") (pinfunction "1_1") (pintype "passive"))
      (node (ref "R3") (pin "1") (pinfunction "1_1") (pintype "passive"))
      (node (ref "R5") (pin "2") (pinfunction "2_2") (pintype "passive"))
      (node (ref "U2") (pin "5") (pinfunction "FB_5") (pintype "input"))
    )
    (net (code "41") (name "Net-(U2-FSW)") (class "Default")
      (node (ref "R4") (pin "2") (pinfunction "2_2") (pintype "passive"))
      (node (ref "U2") (pin "6") (pinfunction "FSW_6") (pintype "passive"))
    )
    (net (code "42") (name "Net-(U2-OUT)") (class "Default")
      (node (ref "L1") (pin "1") (pinfunction "1_1") (pintype "passive"))
      (node (ref "U2") (pin "1") (pinfunction "OUT_1") (pintype "power_in"))
      (node (ref "U5") (pin "1") (pinfunction "CATHODE_1") (pintype "passive"))
    )
    (net (code "43") (name "Net-(U7-ON{slash}OFF)") (class "Default")
      (node (ref "S1") (pin "2") (pinfunction "2_2") (pintype "passive"))
      (node (ref "U7") (pin "5") (pinfunction "ON/OFF_5") (pintype "input"))
    )
    (net (code "44") (name "Net-(U7-R1,C1)") (class "Default")
      (node (ref "R9") (pin "2") (pinfunction "2_2") (pintype "passive"))
      (node (ref "U7") (pin "6") (pinfunction "R1,C1_6") (pintype "input"))
    )
    (net (code "45") (name "V3V3") (class "Default")
      (node (ref "C14") (pin "1") (pinfunction "1_1") (pintype "passive"))
      (node (ref "C15") (pin "1") (pinfunction "1_1") (pintype "passive"))
      (node (ref "C16") (pin "1") (pinfunction "1_1") (pintype "passive"))
      (node (ref "C8") (pin "1") (pinfunction "1_1") (pintype "passive"))
      (node (ref "C9") (pin "1") (pinfunction "1_1") (pintype "passive"))
      (node (ref "CN1") (pin "1") (pinfunction "1_1") (pintype "passive"))
      (node (ref "CN1") (pin "2") (pinfunction "2_2") (pintype "passive"))
      (node (ref "R11") (pin "2") (pinfunction "2_2") (pintype "passive"))
      (node (ref "R16") (pin "1") (pinfunction "1_1") (pintype "passive"))
      (node (ref "R46") (pin "2") (pinfunction "2_2") (pintype "passive"))
      (node (ref "U1") (pin "1") (pinfunction "VBAT_1") (pintype "power_in"))
      (node (ref "U1") (pin "24") (pinfunction "VDD_1_24") (pintype "power_in"))
      (node (ref "U1") (pin "36") (pinfunction "VDD_2_36") (pintype "power_in"))
      (node (ref "U1") (pin "48") (pinfunction "VDD_3_48") (pintype "power_in"))
      (node (ref "U1") (pin "9") (pinfunction "VDDA_9") (pintype "power_in"))
      (node (ref "U6") (pin "2") (pinfunction "VOUT_2") (pintype "power_in"))
      (node (ref "U6") (pin "3") (pinfunction "VOUT_3") (pintype "power_in"))
      (node (ref "U6") (pin "6") (pinfunction "VOUT_6") (pintype "power_in"))
      (node (ref "U6") (pin "7") (pinfunction "VOUT_7") (pintype "power_in"))
      (node (ref "U9") (pin "5") (pinfunction "5_5") (pintype "power_in"))
      (node (ref "VR1") (pin "1") (pinfunction "1_1") (pintype "passive"))
    )
    (net (code "46") (name "V4V5") (class "Default")
      (node (ref "C1") (pin "1") (pinfunction "1_1") (pintype "passive"))
      (node (ref "C2") (pin "1") (pinfunction "1_1") (pintype "passive"))
      (node (ref "C7") (pin "1") (pinfunction "1_1") (pintype "passive"))
      (node (ref "JMP1") (pin "1") (pinfunction "1_1") (pintype "passive"))
      (node (ref "JMP1") (pin "2") (pinfunction "2_2") (pintype "passive"))
      (node (ref "JMP1") (pin "3") (pinfunction "3_3") (pintype "passive"))
      (node (ref "L1") (pin "2") (pinfunction "2_2") (pintype "passive"))
      (node (ref "R1") (pin "2") (pinfunction "2_2") (pintype "passive"))
      (node (ref "U6") (pin "4") (pinfunction "VIN_4") (pintype "power_in"))
    )
    (net (code "47") (name "VBAT") (class "Default")
      (node (ref "Q2") (pin "1") (pinfunction "D_1") (pintype "passive"))
      (node (ref "Q2") (pin "2") (pinfunction "D_2") (pintype "passive"))
      (node (ref "Q2") (pin "5") (pinfunction "D_5") (pintype "passive"))
      (node (ref "Q2") (pin "6") (pinfunction "D_6") (pintype "passive"))
      (node (ref "U3") (pin "1") (pinfunction "K_1") (pintype "passive"))
      (node (ref "U8") (pin "1") (pinfunction "VIN_1") (pintype "power_in"))
    )
    (net (code "48") (name "VEXT") (class "Default")
      (node (ref "C29") (pin "1") (pinfunction "1_1") (pintype "passive"))
      (node (ref "Q1") (pin "4") (pinfunction "S_4") (pintype "passive"))
      (node (ref "Q2") (pin "4") (pinfunction "S_4") (pintype "passive"))
      (node (ref "R8") (pin "1") (pinfunction "1_1") (pintype "passive"))
      (node (ref "R9") (pin "1") (pinfunction "1_1") (pintype "passive"))
      (node (ref "S1") (pin "1") (pinfunction "1_1") (pintype "passive"))
      (node (ref "U7") (pin "4") (pinfunction "VIN,R1_4") (pintype "power_in"))
      (node (ref "U8") (pin "6") (pinfunction "SENSE_6") (pintype "input"))
    )
    (net (code "49") (name "VIN") (class "Default")
      (node (ref "C5") (pin "2") (pinfunction "2_2") (pintype "passive"))
      (node (ref "C6") (pin "2") (pinfunction "2_2") (pintype "passive"))
      (node (ref "U2") (pin "3") (pinfunction "EN_3") (pintype "input"))
      (node (ref "U2") (pin "8") (pinfunction "VCC_8") (pintype "power_in"))
      (node (ref "U7") (pin "2") (pinfunction "VOUT,C1_2_2") (pintype "output"))
      (node (ref "U7") (pin "3") (pinfunction "VOUT,C1_3") (pintype "output"))
    )
    (net (code "50") (name "VUSB") (class "Default")
      (node (ref "P1") (pin "1") (pinfunction "VCC_1") (pintype "power_in"))
      (node (ref "Q1") (pin "1") (pinfunction "D_1") (pintype "passive"))
      (node (ref "Q1") (pin "2") (pinfunction "D_2") (pintype "passive"))
      (node (ref "Q1") (pin "5") (pinfunction "D_5") (pintype "passive"))
      (node (ref "Q1") (pin "6") (pinfunction "D_6") (pintype "passive"))
    )
    (net (code "51") (name "unconnected-(P1-DATA+-Pad3)") (class "Default")
      (node (ref "P1") (pin "3") (pinfunction "DATA+_3") (pintype "bidirectional"))
    )
    (net (code "52") (name "unconnected-(P1-DATA--Pad2)") (class "Default")
      (node (ref "P1") (pin "2") (pinfunction "DATA-_2") (pintype "bidirectional"))
    )
    (net (code "53") (name "unconnected-(P1-ID-Pad4)") (class "Default")
      (node (ref "P1") (pin "4") (pinfunction "ID_4") (pintype "bidirectional"))
    )
    (net (code "54") (name "unconnected-(P2-ID-Pad4)") (class "Default")
      (node (ref "P2") (pin "4") (pinfunction "ID_4") (pintype "bidirectional"))
    )
    (net (code "55") (name "unconnected-(P2-VCC-Pad1)") (class "Default")
      (node (ref "P2") (pin "1") (pinfunction "VCC_1") (pintype "power_in"))
    )
    (net (code "56") (name "unconnected-(U1A-PA2-Pad12)") (class "Default")
      (node (ref "U1") (pin "12") (pinfunction "PA2_12") (pintype "bidirectional"))
    )
    (net (code "57") (name "unconnected-(U1A-PA8-Pad29)") (class "Default")
      (node (ref "U1") (pin "29") (pinfunction "PA8_29") (pintype "bidirectional"))
    )
    (net (code "58") (name "unconnected-(U1A-PA9-Pad30)") (class "Default")
      (node (ref "U1") (pin "30") (pinfunction "PA9_30") (pintype "bidirectional"))
    )
    (net (code "59") (name "unconnected-(U1A-PA10-Pad31)") (class "Default")
      (node (ref "U1") (pin "31") (pinfunction "PA10_31") (pintype "bidirectional"))
    )
    (net (code "60") (name "unconnected-(U1A-PB1-Pad19)") (class "Default")
      (node (ref "U1") (pin "19") (pinfunction "PB1_19") (pintype "bidirectional"))
    )
    (net (code "61") (name "unconnected-(U1A-PB2-Pad20)") (class "Default")
      (node (ref "U1") (pin "20") (pinfunction "PB2_20") (pintype "bidirectional"))
    )
    (net (code "62") (name "unconnected-(U1A-PB5-Pad41)") (class "Default")
      (node (ref "U1") (pin "41") (pinfunction "PB5_41") (pintype "bidirectional"))
    )
    (net (code "63") (name "unconnected-(U1A-PB6-Pad42)") (class "Default")
      (node (ref "U1") (pin "42") (pinfunction "PB6_42") (pintype "bidirectional"))
    )
    (net (code "64") (name "unconnected-(U1A-PB7-Pad43)") (class "Default")
      (node (ref "U1") (pin "43") (pinfunction "PB7_43") (pintype "bidirectional"))
    )
    (net (code "65") (name "unconnected-(U1A-PB8-Pad45)") (class "Default")
      (node (ref "U1") (pin "45") (pinfunction "PB8_45") (pintype "bidirectional"))
    )
    (net (code "66") (name "unconnected-(U1A-PB9-Pad46)") (class "Default")
      (node (ref "U1") (pin "46") (pinfunction "PB9_46") (pintype "bidirectional"))
    )
    (net (code "67") (name "unconnected-(U1A-PB10-Pad21)") (class "Default")
      (node (ref "U1") (pin "21") (pinfunction "PB10_21") (pintype "bidirectional"))
    )
    (net (code "68") (name "unconnected-(U1A-PB11-Pad22)") (class "Default")
      (node (ref "U1") (pin "22") (pinfunction "PB11_22") (pintype "bidirectional"))
    )
    (net (code "69") (name "unconnected-(U1A-PB12-Pad25)") (class "Default")
      (node (ref "U1") (pin "25") (pinfunction "PB12_25") (pintype "bidirectional"))
    )
    (net (code "70") (name "unconnected-(U1A-PB13-Pad26)") (class "Default")
      (node (ref "U1") (pin "26") (pinfunction "PB13_26") (pintype "bidirectional"))
    )
    (net (code "71") (name "unconnected-(U1A-PB14-Pad27)") (class "Default")
      (node (ref "U1") (pin "27") (pinfunction "PB14_27") (pintype "bidirectional"))
    )
    (net (code "72") (name "unconnected-(U1A-PB15-Pad28)") (class "Default")
      (node (ref "U1") (pin "28") (pinfunction "PB15_28") (pintype "bidirectional"))
    )
    (net (code "73") (name "unconnected-(U2-SYNC-Pad2)") (class "Default")
      (node (ref "U2") (pin "2") (pinfunction "SYNC_2") (pintype "passive"))
    )
    (net (code "74") (name "unconnected-(U6-NC-Pad5)") (class "Default")
      (node (ref "U6") (pin "5") (pinfunction "NC_5") (pintype "passive"))
    )
    (net (code "75") (name "unconnected-(U6-NC-Pad8)") (class "Default")
      (node (ref "U6") (pin "8") (pinfunction "NC_8") (pintype "passive"))
    )
  )
)
